# auto_flash.net
KiCad netlist of a schematic drawn in EAGLE
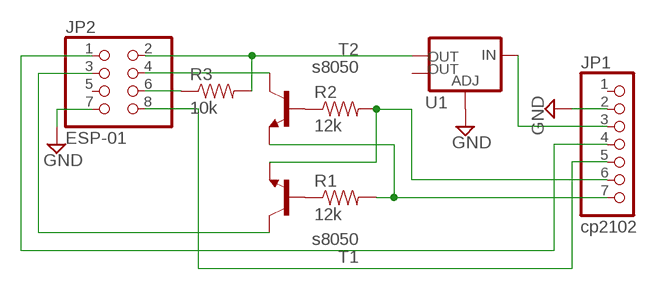
[diagram p0: schematic, sheet 1]

(export (version "E")
  (design (tool "Eeschema 10.0.6"))
  (components
    (comp (ref "JP1")
      (value "cp2102")
      (footprint "eagle-import:1X07_90")
      (libsource (lib "eagle-import") (part "PINHD-1X7/90"))
    )
    (comp (ref "JP2")
      (value "ESP-01")
      (footprint "eagle-import:2X04")
      (libsource (lib "eagle-import") (part "PINHD-2X4"))
    )
    (comp (ref "R1")
      (value "12k")
      (footprint "eagle-import:0805")
      (libsource (lib "eagle-import") (part "0.3OHM-1/8W-1%(0805)"))
    )
    (comp (ref "R2")
      (value "12k")
      (footprint "eagle-import:0805")
      (libsource (lib "eagle-import") (part "0.3OHM-1/8W-1%(0805)"))
    )
    (comp (ref "R3")
      (value "10k")
      (footprint "eagle-import:0805")
      (libsource (lib "eagle-import") (part "0.3OHM-1/8W-1%(0805)"))
    )
    (comp (ref "T1")
      (value "s8050")
      (footprint "eagle-import:TO92-EBC-OVAL")
      (libsource (lib "eagle-import") (part "2N2222"))
    )
    (comp (ref "T2")
      (value "s8050")
      (footprint "eagle-import:TO92-EBC-OVAL")
      (libsource (lib "eagle-import") (part "2N2222"))
    )
    (comp (ref "U1")
      (value "V_REG_LM1117SOT223")
      (footprint "eagle-import:SOT223")
      (libsource (lib "eagle-import") (part "V_REG_LM1117SOT223"))
    )
  )
  (nets
    (net (code "1") (name "GND") (class "Default")
      (node (ref "JP1") (pin "2") (pinfunction "2_2") (pintype "passive"))
      (node (ref "JP2") (pin "7") (pinfunction "7_7") (pintype "passive"))
      (node (ref "U1") (pin "1") (pinfunction "ADJ_1") (pintype "input"))
    )
    (net (code "2") (name "Net-(JP1-Pad4)") (class "Default")
      (node (ref "JP1") (pin "4") (pinfunction "4_4") (pintype "passive"))
      (node (ref "JP2") (pin "1") (pinfunction "1_1") (pintype "passive"))
    )
    (net (code "3") (name "Net-(JP1-Pad5)") (class "Default")
      (node (ref "JP1") (pin "5") (pinfunction "5_5") (pintype "passive"))
      (node (ref "JP2") (pin "8") (pinfunction "8_8") (pintype "passive"))
    )
    (net (code "4") (name "Net-(JP1-Pad6)") (class "Default")
      (node (ref "JP1") (pin "6") (pinfunction "6_6") (pintype "passive"))
      (node (ref "R2") (pin "2") (pinfunction "2_2") (pintype "passive"))
      (node (ref "T1") (pin "E") (pinfunction "E_E") (pintype "passive"))
    )
    (net (code "5") (name "Net-(JP1-Pad7)") (class "Default")
      (node (ref "JP1") (pin "7") (pinfunction "7_7") (pintype "passive"))
      (node (ref "R1") (pin "2") (pinfunction "2_2") (pintype "passive"))
      (node (ref "T2") (pin "E") (pinfunction "E_E") (pintype "passive"))
    )
    (net (code "6") (name "Net-(JP2-Pad2)") (class "Default")
      (node (ref "JP2") (pin "2") (pinfunction "2_2") (pintype "passive"))
      (node (ref "R3") (pin "2") (pinfunction "2_2") (pintype "passive"))
      (node (ref "U1") (pin "2") (pinfunction "OUT_2") (pintype "output"))
    )
    (net (code "7") (name "Net-(JP2-Pad3)") (class "Default")
      (node (ref "JP2") (pin "3") (pinfunction "3_3") (pintype "passive"))
      (node (ref "T1") (pin "C") (pinfunction "C_C") (pintype "passive"))
    )
    (net (code "8") (name "Net-(JP2-Pad4)") (class "Default")
      (node (ref "JP2") (pin "4") (pinfunction "4_4") (pintype "passive"))
      (node (ref "T2") (pin "C") (pinfunction "C_C") (pintype "passive"))
    )
    (net (code "9") (name "Net-(JP2-Pad6)") (class "Default")
      (node (ref "JP2") (pin "6") (pinfunction "6_6") (pintype "passive"))
      (node (ref "R3") (pin "1") (pinfunction "1_1") (pintype "passive"))
    )
    (net (code "10") (name "Net-(R1-Pad1)") (class "Default")
      (node (ref "R1") (pin "1") (pinfunction "1_1") (pintype "passive"))
      (node (ref "T1") (pin "B") (pinfunction "B_B") (pintype "passive"))
    )
    (net (code "11") (name "Net-(R2-Pad1)") (class "Default")
      (node (ref "R2") (pin "1") (pinfunction "1_1") (pintype "passive"))
      (node (ref "T2") (pin "B") (pinfunction "B_B") (pintype "passive"))
    )
    (net (code "12") (name "Net-(U1-IN)") (class "Default")
      (node (ref "JP1") (pin "3") (pinfunction "3_3") (pintype "passive"))
      (node (ref "U1") (pin "3") (pinfunction "IN_3") (pintype "input"))
    )
    (net (code "13") (name "unconnected-(JP1-Pad1)") (class "Default")
      (node (ref "JP1") (pin "1") (pinfunction "1_1") (pintype "passive"))
    )
    (net (code "14") (name "unconnected-(JP2-Pad5)") (class "Default")
      (node (ref "JP2") (pin "5") (pinfunction "5_5") (pintype "passive"))
    )
    (net (code "15") (name "unconnected-(U1-OUT-Pad4)") (class "Default")
      (node (ref "U1") (pin "4") (pinfunction "OUT_4") (pintype "output"))
    )
  )
)
